# Sensor_Connection.net
KiCad netlist of a schematic drawn in Altium Designer
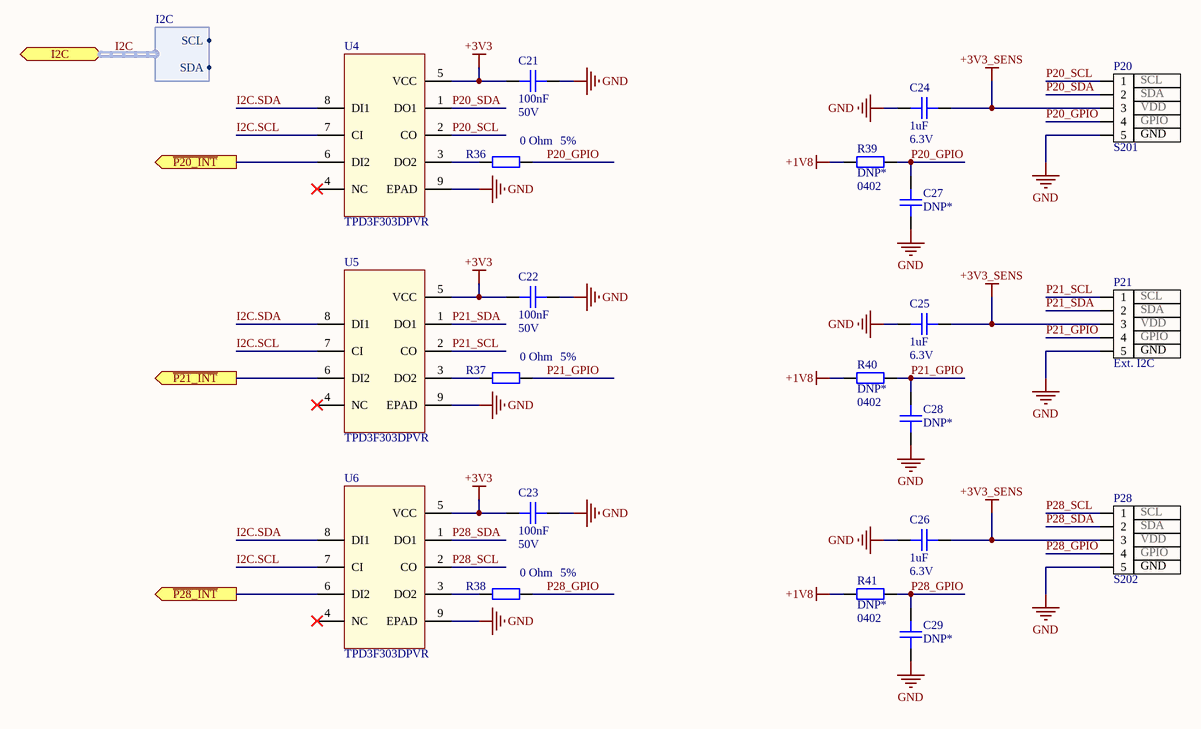
[diagram p0: Sensor Connection.SchDoc]

(export (version "E")
  (design (tool "Eeschema 10.0.6"))
  (components
    (comp (ref "C21")
      (value "CAP CER 0.1UF 50V X7R 0402")
      (footprint "CAP_0402")
      (description "0.1µF ±10% 50V Ceramic Capacitor X7R 0402 (1005 Metric)")
      (fields
        (field (name "MANUFACTURER") "TDK")
        (field (name "MANUFACTURER PART NUMBER") "CGA2B3X7R1H104K050BB")
        (field (name "CAPACITANCE") "100nF")
        (field (name "VOLTAGE") "50V")
      )
      (libsource (lib "capacitors_smd") (part "CAP CER 0.1UF 50V X7R 0402"))
    )
    (comp (ref "C22")
      (value "CAP CER 0.1UF 50V X7R 0402")
      (footprint "CAP_0402")
      (description "0.1µF ±10% 50V Ceramic Capacitor X7R 0402 (1005 Metric)")
      (fields
        (field (name "MANUFACTURER") "TDK")
        (field (name "MANUFACTURER PART NUMBER") "CGA2B3X7R1H104K050BB")
        (field (name "CAPACITANCE") "100nF")
        (field (name "VOLTAGE") "50V")
      )
      (libsource (lib "capacitors_smd") (part "CAP CER 0.1UF 50V X7R 0402"))
    )
    (comp (ref "C23")
      (value "CAP CER 0.1UF 50V X7R 0402")
      (footprint "CAP_0402")
      (description "0.1µF ±10% 50V Ceramic Capacitor X7R 0402 (1005 Metric)")
      (fields
        (field (name "MANUFACTURER") "TDK")
        (field (name "MANUFACTURER PART NUMBER") "CGA2B3X7R1H104K050BB")
        (field (name "CAPACITANCE") "100nF")
        (field (name "VOLTAGE") "50V")
      )
      (libsource (lib "capacitors_smd") (part "CAP CER 0.1UF 50V X7R 0402"))
    )
    (comp (ref "C24")
      (value "CAP CER 1UF 6.3V X5R 0402")
      (footprint "CAP_0402")
      (description "1µF ±10% 6.3V Ceramic Capacitor X5R 0402 (1005 Metric)")
      (fields
        (field (name "MANUFACTURER") "Yageo")
        (field (name "MANUFACTURER PART NUMBER") "CC0402KRX5R5BB105")
        (field (name "CAPACITANCE") "1uF")
        (field (name "VOLTAGE RATING") "6.3V")
      )
      (libsource (lib "capacitors_smd") (part "CAP CER 1UF 6.3V X5R 0402"))
    )
    (comp (ref "C25")
      (value "CAP CER 1UF 6.3V X5R 0402")
      (footprint "CAP_0402")
      (description "1µF ±10% 6.3V Ceramic Capacitor X5R 0402 (1005 Metric)")
      (fields
        (field (name "MANUFACTURER") "Yageo")
        (field (name "MANUFACTURER PART NUMBER") "CC0402KRX5R5BB105")
        (field (name "CAPACITANCE") "1uF")
        (field (name "VOLTAGE RATING") "6.3V")
      )
      (libsource (lib "capacitors_smd") (part "CAP CER 1UF 6.3V X5R 0402"))
    )
    (comp (ref "C26")
      (value "CAP CER 1UF 6.3V X5R 0402")
      (footprint "CAP_0402")
      (description "1µF ±10% 6.3V Ceramic Capacitor X5R 0402 (1005 Metric)")
      (fields
        (field (name "MANUFACTURER") "Yageo")
        (field (name "MANUFACTURER PART NUMBER") "CC0402KRX5R5BB105")
        (field (name "CAPACITANCE") "1uF")
        (field (name "VOLTAGE RATING") "6.3V")
      )
      (libsource (lib "capacitors_smd") (part "CAP CER 1UF 6.3V X5R 0402"))
    )
    (comp (ref "C27")
      (value "DNP*")
      (footprint "C0402")
      (description "Placeholder for a 0402 capacitor")
      (libsource (lib "capacitors_smd") (part "CAP CER NO_BOM 0402"))
    )
    (comp (ref "C28")
      (value "DNP*")
      (footprint "C0402")
      (description "Placeholder for a 0402 capacitor")
      (libsource (lib "capacitors_smd") (part "CAP CER NO_BOM 0402"))
    )
    (comp (ref "C29")
      (value "DNP*")
      (footprint "C0402")
      (description "Placeholder for a 0402 capacitor")
      (libsource (lib "capacitors_smd") (part "CAP CER NO_BOM 0402"))
    )
    (comp (ref "P20")
      (value "S201")
      (footprint "CONN_S5B-ZR(LF)(SN)")
      (description "Connector Header Through Hole, Right Angle 5 position 0.059\" (1.50mm)")
      (fields
        (field (name "MANUFACTURER") "JST")
        (field (name "MANUFACTURER PART NUMBER") "S5B-ZR(LF)(SN)")
        (field (name "PIN_1") "SCL")
        (field (name "PIN_2") "SDA")
        (field (name "PIN_3") "VDD")
        (field (name "PIN_4") "GPIO")
        (field (name "PIN_5") "GND")
      )
      (libsource (lib "connectors_header") (part "CONN HEADER TH R/A 5POS 1.5MM"))
    )
    (comp (ref "P21")
      (value "Ext. I2C")
      (footprint "CONN_S5B-ZR(LF)(SN)")
      (description "Connector Header Through Hole, Right Angle 5 position 0.059\" (1.50mm)")
      (fields
        (field (name "MANUFACTURER") "JST")
        (field (name "MANUFACTURER PART NUMBER") "S5B-ZR(LF)(SN)")
        (field (name "PIN_1") "SCL")
        (field (name "PIN_2") "SDA")
        (field (name "PIN_3") "VDD")
        (field (name "PIN_4") "GPIO")
        (field (name "PIN_5") "GND")
      )
      (libsource (lib "connectors_header") (part "CONN HEADER TH R/A 5POS 1.5MM"))
    )
    (comp (ref "P28")
      (value "S202")
      (footprint "CONN_S5B-ZR(LF)(SN)")
      (description "Connector Header Through Hole, Right Angle 5 position 0.059\" (1.50mm)")
      (fields
        (field (name "MANUFACTURER") "JST")
        (field (name "MANUFACTURER PART NUMBER") "S5B-ZR(LF)(SN)")
        (field (name "PIN_1") "SCL")
        (field (name "PIN_2") "SDA")
        (field (name "PIN_3") "VDD")
        (field (name "PIN_4") "GPIO")
        (field (name "PIN_5") "GND")
      )
      (libsource (lib "connectors_header") (part "CONN HEADER TH R/A 5POS 1.5MM"))
    )
    (comp (ref "R36")
      (value "RES SMD 0 OHM JUMPER 1/16W 0402")
      (footprint "0402R")
      (description "0 Ohms Jumper 0.063W, 1/16W Chip Resistor 0402 (1005 Metric) Moisture Resistant Thick Film")
      (fields
        (field (name "MANUFACTURER") "Yageo")
        (field (name "MANUFACTURER PART NUMBER") "RC0402JR-070RL")
        (field (name "TOLERANCE") "5%")
        (field (name "RESISTANCE") "0 Ohm")
      )
      (libsource (lib "resistors_smd") (part "RES SMD 0 OHM JUMPER 1/16W 0402"))
    )
    (comp (ref "R37")
      (value "RES SMD 0 OHM JUMPER 1/16W 0402")
      (footprint "0402R")
      (description "0 Ohms Jumper 0.063W, 1/16W Chip Resistor 0402 (1005 Metric) Moisture Resistant Thick Film")
      (fields
        (field (name "MANUFACTURER") "Yageo")
        (field (name "MANUFACTURER PART NUMBER") "RC0402JR-070RL")
        (field (name "TOLERANCE") "5%")
        (field (name "RESISTANCE") "0 Ohm")
      )
      (libsource (lib "resistors_smd") (part "RES SMD 0 OHM JUMPER 1/16W 0402"))
    )
    (comp (ref "R38")
      (value "RES SMD 0 OHM JUMPER 1/16W 0402")
      (footprint "0402R")
      (description "0 Ohms Jumper 0.063W, 1/16W Chip Resistor 0402 (1005 Metric) Moisture Resistant Thick Film")
      (fields
        (field (name "MANUFACTURER") "Yageo")
        (field (name "MANUFACTURER PART NUMBER") "RC0402JR-070RL")
        (field (name "TOLERANCE") "5%")
        (field (name "RESISTANCE") "0 Ohm")
      )
      (libsource (lib "resistors_smd") (part "RES SMD 0 OHM JUMPER 1/16W 0402"))
    )
    (comp (ref "R39")
      (value "DNP*")
      (footprint "0402R")
      (description "Placeholder for a 0402 resistor")
      (fields (field (name "CASE/PACKAGE") "0402"))
      (libsource (lib "resistors_smd") (part "RES SMD NO BOM 0402"))
    )
    (comp (ref "R40")
      (value "DNP*")
      (footprint "0402R")
      (description "Placeholder for a 0402 resistor")
      (fields (field (name "CASE/PACKAGE") "0402"))
      (libsource (lib "resistors_smd") (part "RES SMD NO BOM 0402"))
    )
    (comp (ref "R41")
      (value "DNP*")
      (footprint "0402R")
      (description "Placeholder for a 0402 resistor")
      (fields (field (name "CASE/PACKAGE") "0402"))
      (libsource (lib "resistors_smd") (part "RES SMD NO BOM 0402"))
    )
    (comp (ref "U4")
      (value "TPD3F303DPVR")
      (footprint "DPV8_1P7X0P4")
      (description "RC (Pi) EMI Filter 2nd Order Low Pass 3 Channel R = 47Ohms, 100Ohms, C = 20pF  8-UFDFN Exposed Pad")
      (fields (field (name "MANUFACTURER") "Texas Instruments"))
      (libsource (lib "diodes_tvs") (part "FILTER RC(PI) ESD SMD  8-UFDFN EP"))
    )
    (comp (ref "U5")
      (value "TPD3F303DPVR")
      (footprint "DPV8_1P7X0P4")
      (description "RC (Pi) EMI Filter 2nd Order Low Pass 3 Channel R = 47Ohms, 100Ohms, C = 20pF  8-UFDFN Exposed Pad")
      (fields (field (name "MANUFACTURER") "Texas Instruments"))
      (libsource (lib "diodes_tvs") (part "FILTER RC(PI) ESD SMD  8-UFDFN EP"))
    )
    (comp (ref "U6")
      (value "TPD3F303DPVR")
      (footprint "DPV8_1P7X0P4")
      (description "RC (Pi) EMI Filter 2nd Order Low Pass 3 Channel R = 47Ohms, 100Ohms, C = 20pF  8-UFDFN Exposed Pad")
      (fields (field (name "MANUFACTURER") "Texas Instruments"))
      (libsource (lib "diodes_tvs") (part "FILTER RC(PI) ESD SMD  8-UFDFN EP"))
    )
  )
  (nets
    (net (code "2") (name "+1V8") (class "Default")
      (node (ref "R39") (pin "2") (pinfunction "2_2") (pintype "passive"))
      (node (ref "R40") (pin "2") (pinfunction "2_2") (pintype "passive"))
      (node (ref "R41") (pin "2") (pinfunction "2_2") (pintype "passive"))
    )
    (net (code "3") (name "+3V3") (class "Default")
      (node (ref "C21") (pin "1") (pinfunction "1_1") (pintype "passive"))
      (node (ref "C22") (pin "1") (pinfunction "1_1") (pintype "passive"))
      (node (ref "C23") (pin "1") (pinfunction "1_1") (pintype "passive"))
      (node (ref "U4") (pin "5") (pinfunction "VCC_5") (pintype "power_in"))
      (node (ref "U5") (pin "5") (pinfunction "VCC_5") (pintype "power_in"))
      (node (ref "U6") (pin "5") (pinfunction "VCC_5") (pintype "power_in"))
    )
    (net (code "4") (name "+3V3_SENS") (class "Default")
      (node (ref "C24") (pin "2") (pinfunction "2_2") (pintype "passive"))
      (node (ref "C25") (pin "2") (pinfunction "2_2") (pintype "passive"))
      (node (ref "C26") (pin "2") (pinfunction "2_2") (pintype "passive"))
      (node (ref "P20") (pin "3") (pinfunction "3_3") (pintype "passive"))
      (node (ref "P21") (pin "3") (pinfunction "3_3") (pintype "passive"))
      (node (ref "P28") (pin "3") (pinfunction "3_3") (pintype "passive"))
    )
    (net (code "5") (name "/I2C.SCL") (class "Default")
      (node (ref "U4") (pin "7") (pinfunction "CI_7") (pintype "passive"))
      (node (ref "U5") (pin "7") (pinfunction "CI_7") (pintype "passive"))
      (node (ref "U6") (pin "7") (pinfunction "CI_7") (pintype "passive"))
    )
    (net (code "6") (name "/I2C.SDA") (class "Default")
      (node (ref "U4") (pin "8") (pinfunction "DI1_8") (pintype "passive"))
      (node (ref "U5") (pin "8") (pinfunction "DI1_8") (pintype "passive"))
      (node (ref "U6") (pin "8") (pinfunction "DI1_8") (pintype "passive"))
    )
    (net (code "8") (name "/P20_GPIO") (class "Default")
      (node (ref "C27") (pin "2") (pinfunction "2_2") (pintype "passive"))
      (node (ref "P20") (pin "4") (pinfunction "4_4") (pintype "passive"))
      (node (ref "R36") (pin "2") (pinfunction "2_2") (pintype "passive"))
      (node (ref "R39") (pin "1") (pinfunction "1_1") (pintype "passive"))
    )
    (net (code "9") (name "/P20_INT") (class "Default")
      (node (ref "U4") (pin "6") (pinfunction "DI2_6") (pintype "passive"))
    )
    (net (code "10") (name "/P20_SCL") (class "Default")
      (node (ref "P20") (pin "1") (pinfunction "1_1") (pintype "passive"))
      (node (ref "U4") (pin "2") (pinfunction "CO_2") (pintype "passive"))
    )
    (net (code "11") (name "/P20_SDA") (class "Default")
      (node (ref "P20") (pin "2") (pinfunction "2_2") (pintype "passive"))
      (node (ref "U4") (pin "1") (pinfunction "DO1_1") (pintype "passive"))
    )
    (net (code "12") (name "/P21_GPIO") (class "Default")
      (node (ref "C28") (pin "2") (pinfunction "2_2") (pintype "passive"))
      (node (ref "P21") (pin "4") (pinfunction "4_4") (pintype "passive"))
      (node (ref "R37") (pin "2") (pinfunction "2_2") (pintype "passive"))
      (node (ref "R40") (pin "1") (pinfunction "1_1") (pintype "passive"))
    )
    (net (code "13") (name "/P21_INT") (class "Default")
      (node (ref "U5") (pin "6") (pinfunction "DI2_6") (pintype "passive"))
    )
    (net (code "14") (name "/P21_SCL") (class "Default")
      (node (ref "P21") (pin "1") (pinfunction "1_1") (pintype "passive"))
      (node (ref "U5") (pin "2") (pinfunction "CO_2") (pintype "passive"))
    )
    (net (code "15") (name "/P21_SDA") (class "Default")
      (node (ref "P21") (pin "2") (pinfunction "2_2") (pintype "passive"))
      (node (ref "U5") (pin "1") (pinfunction "DO1_1") (pintype "passive"))
    )
    (net (code "16") (name "/P28_GPIO") (class "Default")
      (node (ref "C29") (pin "2") (pinfunction "2_2") (pintype "passive"))
      (node (ref "P28") (pin "4") (pinfunction "4_4") (pintype "passive"))
      (node (ref "R38") (pin "2") (pinfunction "2_2") (pintype "passive"))
      (node (ref "R41") (pin "1") (pinfunction "1_1") (pintype "passive"))
    )
    (net (code "17") (name "/P28_INT") (class "Default")
      (node (ref "U6") (pin "6") (pinfunction "DI2_6") (pintype "passive"))
    )
    (net (code "18") (name "/P28_SCL") (class "Default")
      (node (ref "P28") (pin "1") (pinfunction "1_1") (pintype "passive"))
      (node (ref "U6") (pin "2") (pinfunction "CO_2") (pintype "passive"))
    )
    (net (code "19") (name "/P28_SDA") (class "Default")
      (node (ref "P28") (pin "2") (pinfunction "2_2") (pintype "passive"))
      (node (ref "U6") (pin "1") (pinfunction "DO1_1") (pintype "passive"))
    )
    (net (code "20") (name "GND") (class "Default")
      (node (ref "C21") (pin "2") (pinfunction "2_2") (pintype "passive"))
      (node (ref "C22") (pin "2") (pinfunction "2_2") (pintype "passive"))
      (node (ref "C23") (pin "2") (pinfunction "2_2") (pintype "passive"))
      (node (ref "C24") (pin "1") (pinfunction "1_1") (pintype "passive"))
      (node (ref "C25") (pin "1") (pinfunction "1_1") (pintype "passive"))
      (node (ref "C26") (pin "1") (pinfunction "1_1") (pintype "passive"))
      (node (ref "C27") (pin "1") (pinfunction "1_1") (pintype "passive"))
      (node (ref "C28") (pin "1") (pinfunction "1_1") (pintype "passive"))
      (node (ref "C29") (pin "1") (pinfunction "1_1") (pintype "passive"))
      (node (ref "P20") (pin "5") (pinfunction "5_5") (pintype "passive"))
      (node (ref "P21") (pin "5") (pinfunction "5_5") (pintype "passive"))
      (node (ref "P28") (pin "5") (pinfunction "5_5") (pintype "passive"))
      (node (ref "U4") (pin "9") (pinfunction "EPAD_9") (pintype "passive"))
      (node (ref "U5") (pin "9") (pinfunction "EPAD_9") (pintype "passive"))
      (node (ref "U6") (pin "9") (pinfunction "EPAD_9") (pintype "passive"))
    )
    (net (code "21") (name "Net-(U4-DO2)") (class "Default")
      (node (ref "R36") (pin "1") (pinfunction "1_1") (pintype "passive"))
      (node (ref "U4") (pin "3") (pinfunction "DO2_3") (pintype "passive"))
    )
    (net (code "22") (name "Net-(U5-DO2)") (class "Default")
      (node (ref "R37") (pin "1") (pinfunction "1_1") (pintype "passive"))
      (node (ref "U5") (pin "3") (pinfunction "DO2_3") (pintype "passive"))
    )
    (net (code "23") (name "Net-(U6-DO2)") (class "Default")
      (node (ref "R38") (pin "1") (pinfunction "1_1") (pintype "passive"))
      (node (ref "U6") (pin "3") (pinfunction "DO2_3") (pintype "passive"))
    )
    (net (code "24") (name "unconnected-(U4-NC-Pad4)") (class "Default")
      (node (ref "U4") (pin "4") (pinfunction "NC_4") (pintype "passive+no_connect"))
    )
    (net (code "25") (name "unconnected-(U5-NC-Pad4)") (class "Default")
      (node (ref "U5") (pin "4") (pinfunction "NC_4") (pintype "passive+no_connect"))
    )
    (net (code "26") (name "unconnected-(U6-NC-Pad4)") (class "Default")
      (node (ref "U6") (pin "4") (pinfunction "NC_4") (pintype "passive+no_connect"))
    )
  )
)
